# Output_terminals.net
KiCad netlist of a schematic drawn in Altium Designer
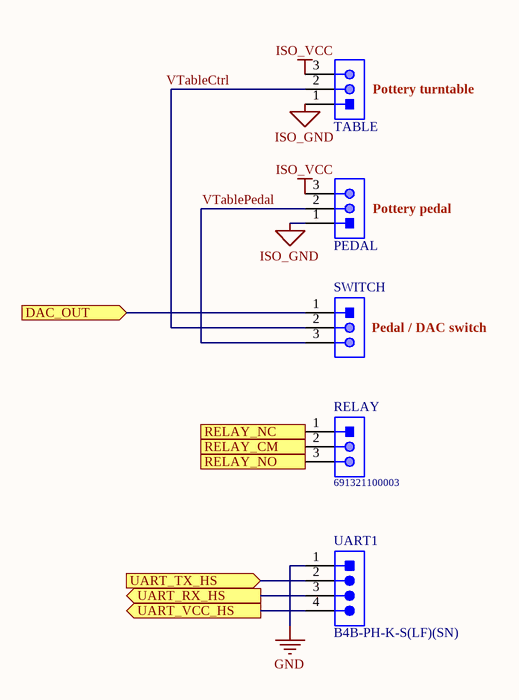
[diagram p0: Output terminals.SchDoc]

(export (version "E")
  (design (tool "Eeschema 10.0.6"))
  (components
    (comp (ref "PEDAL")
      (value "691321300003")
      (footprint "691321300003")
      (description "Serie 321 - 3.81mm Vertical PCB Header WR-TBL, 3 pin")
      (fields (field (name "MANUFACTURER") "Wurth Elektronik") (field (name "PUBLISHER") "WurthElektronik"))
      (libsource (lib "Altium Content Vault") (part "WE-CN-1P-M-R3"))
    )
    (comp (ref "RELAY")
      (value "691321100003")
      (footprint "691321100003")
      (description "Serie 3211 - 3.50mm Vertical PCB Header WR-TBL, 3 pin")
      (fields (field (name "MANUFACTURER") "Wurth Elektronik") (field (name "PUBLISHER") "WurthElektronik"))
      (libsource (lib "") (part "WE-CN-1P-M-R3_1"))
    )
    (comp (ref "SWITCH")
      (value "691321300003")
      (footprint "691321300003")
      (description "Serie 321 - 3.81mm Vertical PCB Header WR-TBL, 3 pin")
      (fields (field (name "MANUFACTURER") "Wurth Elektronik") (field (name "PUBLISHER") "WurthElektronik"))
      (libsource (lib "") (part "WE-CN-1P-M-R3_1"))
    )
    (comp (ref "TABLE")
      (value "691321300003")
      (footprint "691321300003")
      (description "Serie 321 - 3.81mm Vertical PCB Header WR-TBL, 3 pin")
      (fields (field (name "MANUFACTURER") "Wurth Elektronik") (field (name "PUBLISHER") "WurthElektronik"))
      (libsource (lib "Altium Content Vault") (part "WE-CN-1P-M-R3"))
    )
    (comp (ref "UART1")
      (value "B4B-PH-K-S(LF)(SN)")
      (footprint "JST-B4B-PH-K-S_V")
      (fields (field (name "MANUFACTURER") "JST"))
      (libsource (lib "Altium Content Vault") (part "CN-1P-M-R4"))
    )
  )
  (nets
    (net (code "1") (name "/DAC_OUT") (class "Default")
      (node (ref "SWITCH") (pin "1") (pinfunction "1_1") (pintype "passive"))
    )
    (net (code "2") (name "/RELAY_CM") (class "Default")
      (node (ref "RELAY") (pin "2") (pinfunction "2_2") (pintype "passive"))
    )
    (net (code "3") (name "/RELAY_NC") (class "Default")
      (node (ref "RELAY") (pin "1") (pinfunction "1_1") (pintype "passive"))
    )
    (net (code "4") (name "/RELAY_NO") (class "Default")
      (node (ref "RELAY") (pin "3") (pinfunction "3_3") (pintype "passive"))
    )
    (net (code "5") (name "/UART_RX_HS") (class "Default")
      (node (ref "UART1") (pin "3") (pinfunction "3_3") (pintype "passive"))
    )
    (net (code "6") (name "/UART_TX_HS") (class "Default")
      (node (ref "UART1") (pin "2") (pinfunction "2_2") (pintype "passive"))
    )
    (net (code "7") (name "/UART_VCC_HS") (class "Default")
      (node (ref "UART1") (pin "4") (pinfunction "4_4") (pintype "passive"))
    )
    (net (code "8") (name "/VTableCtrl") (class "Default")
      (node (ref "SWITCH") (pin "2") (pinfunction "2_2") (pintype "passive"))
      (node (ref "TABLE") (pin "2") (pinfunction "2_2") (pintype "passive"))
    )
    (net (code "9") (name "/VTablePedal") (class "Default")
      (node (ref "PEDAL") (pin "2") (pinfunction "2_2") (pintype "passive"))
      (node (ref "SWITCH") (pin "3") (pinfunction "3_3") (pintype "passive"))
    )
    (net (code "10") (name "GND") (class "Default")
      (node (ref "UART1") (pin "1") (pinfunction "1_1") (pintype "passive"))
    )
    (net (code "11") (name "ISO_GND") (class "Default")
      (node (ref "PEDAL") (pin "1") (pinfunction "1_1") (pintype "passive"))
      (node (ref "TABLE") (pin "1") (pinfunction "1_1") (pintype "passive"))
    )
    (net (code "12") (name "ISO_VCC") (class "Default")
      (node (ref "PEDAL") (pin "3") (pinfunction "3_3") (pintype "passive"))
      (node (ref "TABLE") (pin "3") (pinfunction "3_3") (pintype "passive"))
    )
  )
)
